# ece411_t2_schematic_11_15.net
KiCad netlist of a schematic drawn in EAGLE
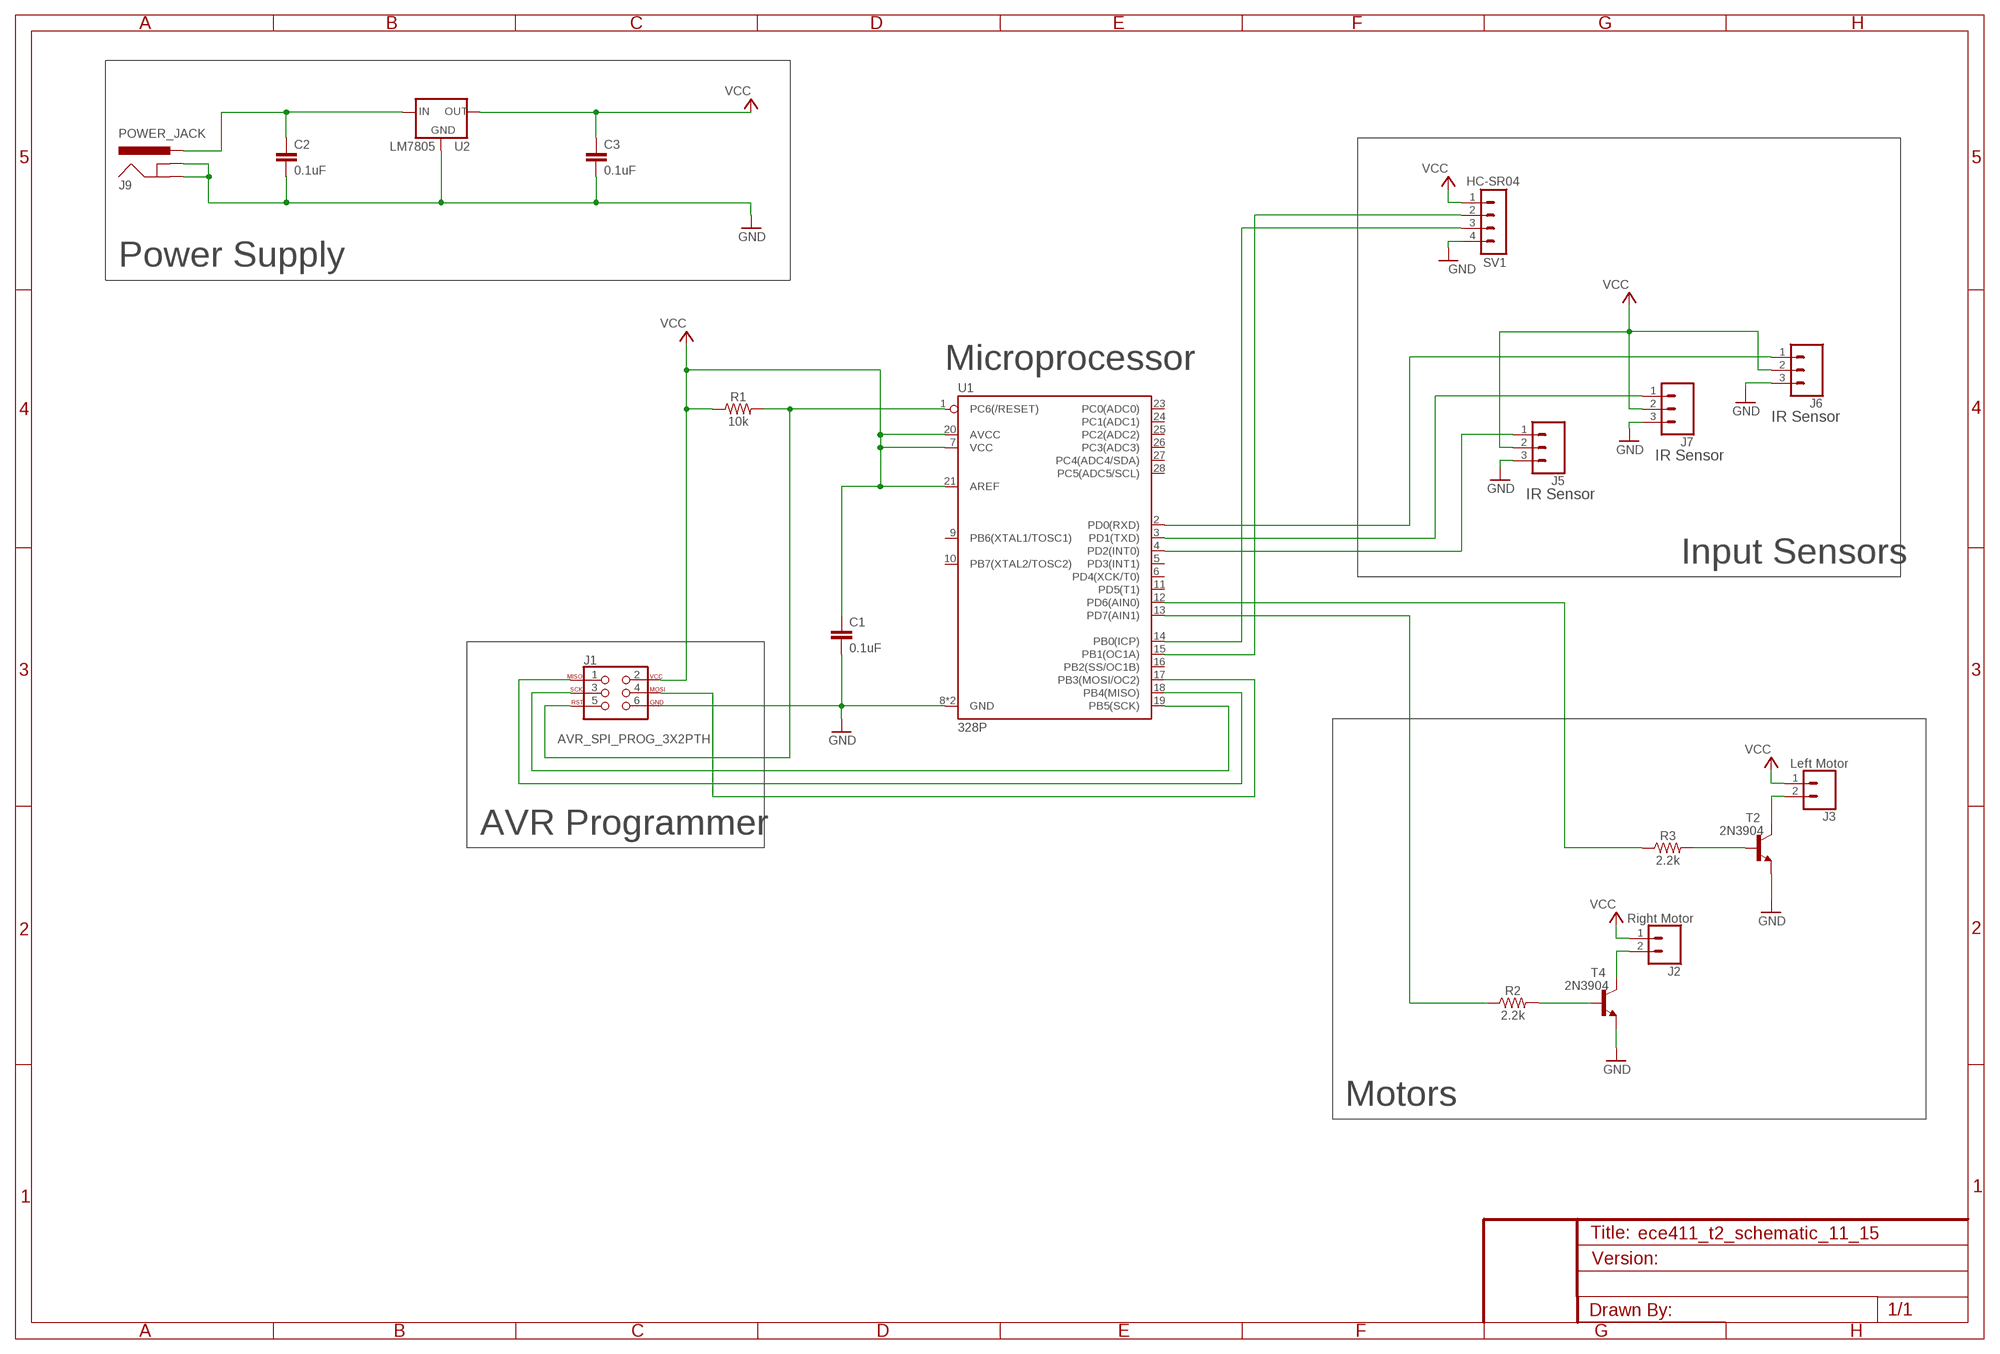
[diagram p0: schematic, sheet 1]

(export (version "E")
  (design (tool "Eeschema 10.0.6"))
  (components
    (comp (ref "C1")
      (value "0.1uF")
      (footprint "eagle-import:0402")
      (libsource (lib "eagle-import") (part "0.1UF-0402-6.3V-10%-X7R"))
    )
    (comp (ref "C2")
      (value "0.1uF")
      (footprint "eagle-import:0402")
      (libsource (lib "eagle-import") (part "0.1UF-0402-6.3V-10%-X7R"))
    )
    (comp (ref "C3")
      (value "0.1uF")
      (footprint "eagle-import:0402")
      (libsource (lib "eagle-import") (part "0.1UF-0402-6.3V-10%-X7R"))
    )
    (comp (ref "J1")
      (value "AVR_SPI_PROG_3X2PTH")
      (footprint "eagle-import:2X3")
      (libsource (lib "eagle-import") (part "AVR_SPI_PROG_3X2PTH"))
    )
    (comp (ref "J2")
      (value "Right Motor")
      (footprint "eagle-import:1X02")
      (libsource (lib "eagle-import") (part "CONN_02"))
    )
    (comp (ref "J3")
      (value "Left Motor")
      (footprint "eagle-import:1X02")
      (libsource (lib "eagle-import") (part "CONN_02"))
    )
    (comp (ref "J5")
      (value "455-1750-1-ND")
      (footprint "eagle-import:1X03")
      (libsource (lib "eagle-import") (part "CONN_03"))
    )
    (comp (ref "J6")
      (value "455-1750-1-ND")
      (footprint "eagle-import:1X03")
      (libsource (lib "eagle-import") (part "CONN_03"))
    )
    (comp (ref "J7")
      (value "455-1750-1-ND")
      (footprint "eagle-import:1X03")
      (libsource (lib "eagle-import") (part "CONN_03"))
    )
    (comp (ref "J9")
      (value "POWER_JACK")
      (footprint "eagle-import:POWER_JACK_PTH")
      (libsource (lib "eagle-import") (part "POWER_JACK"))
    )
    (comp (ref "R1")
      (value "10k")
      (footprint "eagle-import:0402")
      (libsource (lib "eagle-import") (part "10KOHM-0402-1/16W-1%"))
    )
    (comp (ref "R2")
      (value "2.2k")
      (footprint "eagle-import:0603")
      (libsource (lib "eagle-import") (part "2.2KOHM-0603-1/10W-1%"))
    )
    (comp (ref "R3")
      (value "2.2k")
      (footprint "eagle-import:0603")
      (libsource (lib "eagle-import") (part "2.2KOHM-0603-1/10W-1%"))
    )
    (comp (ref "SV1")
      (value "HC-SR04")
      (footprint "eagle-import:MA04-1")
      (libsource (lib "eagle-import") (part "MA04-1"))
    )
    (comp (ref "T2")
      (value "2N3904")
      (footprint "eagle-import:TO92")
      (libsource (lib "eagle-import") (part "2N3904"))
    )
    (comp (ref "T4")
      (value "2N3904")
      (footprint "eagle-import:TO92")
      (libsource (lib "eagle-import") (part "2N3904"))
    )
    (comp (ref "U1")
      (value "328P")
      (footprint "eagle-import:DIP28")
      (libsource (lib "eagle-import") (part "ATMEGA328P_PDIP"))
    )
    (comp (ref "U2")
      (value "LM7805")
      (footprint "eagle-import:TO-220-ALT")
      (libsource (lib "eagle-import") (part "V_REG_78XX-TO-220"))
    )
  )
  (nets
    (net (code "1") (name "GND") (class "Default")
      (node (ref "C1") (pin "2") (pinfunction "2_2") (pintype "passive"))
      (node (ref "C2") (pin "2") (pinfunction "2_2") (pintype "passive"))
      (node (ref "C3") (pin "2") (pinfunction "2_2") (pintype "passive"))
      (node (ref "J1") (pin "6") (pinfunction "6_6") (pintype "passive"))
      (node (ref "J5") (pin "3") (pinfunction "3_3") (pintype "passive"))
      (node (ref "J6") (pin "3") (pinfunction "3_3") (pintype "passive"))
      (node (ref "J7") (pin "3") (pinfunction "3_3") (pintype "passive"))
      (node (ref "J9") (pin "GND") (pinfunction "GND_GND") (pintype "bidirectional"))
      (node (ref "J9") (pin "GNDBREAK") (pinfunction "GNDBREAK_GNDBREAK") (pintype "bidirectional"))
      (node (ref "SV1") (pin "4") (pinfunction "4_4") (pintype "passive"))
      (node (ref "T2") (pin "3") (pinfunction "E_3") (pintype "passive"))
      (node (ref "T4") (pin "3") (pinfunction "E_3") (pintype "passive"))
      (node (ref "U1") (pin "22") (pinfunction "GND_22") (pintype "bidirectional"))
      (node (ref "U1") (pin "8") (pinfunction "GND_8") (pintype "bidirectional"))
      (node (ref "U2") (pin "GND") (pinfunction "GND_GND") (pintype "input"))
    )
    (net (code "2") (name "Net-(C2-Pad1)") (class "Default")
      (node (ref "C2") (pin "1") (pinfunction "1_1") (pintype "passive"))
      (node (ref "J9") (pin "PWR") (pinfunction "PWR_PWR") (pintype "bidirectional"))
      (node (ref "U2") (pin "IN") (pinfunction "IN_IN") (pintype "input"))
    )
    (net (code "3") (name "Net-(T2-B)") (class "Default")
      (node (ref "R3") (pin "2") (pinfunction "2_2") (pintype "passive"))
      (node (ref "T2") (pin "2") (pinfunction "B_2") (pintype "passive"))
    )
    (net (code "4") (name "Net-(T2-C)") (class "Default")
      (node (ref "J3") (pin "2") (pinfunction "2_2") (pintype "passive"))
      (node (ref "T2") (pin "1") (pinfunction "C_1") (pintype "passive"))
    )
    (net (code "5") (name "Net-(T4-B)") (class "Default")
      (node (ref "R2") (pin "2") (pinfunction "2_2") (pintype "passive"))
      (node (ref "T4") (pin "2") (pinfunction "B_2") (pintype "passive"))
    )
    (net (code "6") (name "Net-(T4-C)") (class "Default")
      (node (ref "J2") (pin "2") (pinfunction "2_2") (pintype "passive"))
      (node (ref "T4") (pin "1") (pinfunction "C_1") (pintype "passive"))
    )
    (net (code "7") (name "Net-(U1-PB0(ICP))") (class "Default")
      (node (ref "SV1") (pin "3") (pinfunction "3_3") (pintype "passive"))
      (node (ref "U1") (pin "14") (pinfunction "PB0(ICP)_14") (pintype "bidirectional"))
    )
    (net (code "8") (name "Net-(U1-PB1(OC1A))") (class "Default")
      (node (ref "SV1") (pin "2") (pinfunction "2_2") (pintype "passive"))
      (node (ref "U1") (pin "15") (pinfunction "PB1(OC1A)_15") (pintype "bidirectional"))
    )
    (net (code "9") (name "Net-(U1-PB3(MOSI{slash}OC2))") (class "Default")
      (node (ref "J1") (pin "4") (pinfunction "4_4") (pintype "passive"))
      (node (ref "U1") (pin "17") (pinfunction "PB3(MOSI/OC2)_17") (pintype "bidirectional"))
    )
    (net (code "10") (name "Net-(U1-PB4(MISO))") (class "Default")
      (node (ref "J1") (pin "1") (pinfunction "1_1") (pintype "passive"))
      (node (ref "U1") (pin "18") (pinfunction "PB4(MISO)_18") (pintype "bidirectional"))
    )
    (net (code "11") (name "Net-(U1-PB5(SCK))") (class "Default")
      (node (ref "J1") (pin "3") (pinfunction "3_3") (pintype "passive"))
      (node (ref "U1") (pin "19") (pinfunction "PB5(SCK)_19") (pintype "bidirectional"))
    )
    (net (code "12") (name "Net-(U1-PC6({slash}RESET))") (class "Default")
      (node (ref "J1") (pin "5") (pinfunction "5_5") (pintype "passive"))
      (node (ref "R1") (pin "2") (pinfunction "2_2") (pintype "passive"))
      (node (ref "U1") (pin "1") (pinfunction "PC6(/RESET)_1") (pintype "bidirectional"))
    )
    (net (code "13") (name "Net-(U1-PD0(RXD))") (class "Default")
      (node (ref "J6") (pin "1") (pinfunction "1_1") (pintype "passive"))
      (node (ref "U1") (pin "2") (pinfunction "PD0(RXD)_2") (pintype "bidirectional"))
    )
    (net (code "14") (name "Net-(U1-PD1(TXD))") (class "Default")
      (node (ref "J7") (pin "1") (pinfunction "1_1") (pintype "passive"))
      (node (ref "U1") (pin "3") (pinfunction "PD1(TXD)_3") (pintype "bidirectional"))
    )
    (net (code "15") (name "Net-(U1-PD2(INT0))") (class "Default")
      (node (ref "J5") (pin "1") (pinfunction "1_1") (pintype "passive"))
      (node (ref "U1") (pin "4") (pinfunction "PD2(INT0)_4") (pintype "bidirectional"))
    )
    (net (code "16") (name "Net-(U1-PD6(AIN0))") (class "Default")
      (node (ref "R3") (pin "1") (pinfunction "1_1") (pintype "passive"))
      (node (ref "U1") (pin "12") (pinfunction "PD6(AIN0)_12") (pintype "bidirectional"))
    )
    (net (code "17") (name "Net-(U1-PD7(AIN1))") (class "Default")
      (node (ref "R2") (pin "1") (pinfunction "1_1") (pintype "passive"))
      (node (ref "U1") (pin "13") (pinfunction "PD7(AIN1)_13") (pintype "bidirectional"))
    )
    (net (code "18") (name "VCC") (class "Default")
      (node (ref "C1") (pin "1") (pinfunction "1_1") (pintype "passive"))
      (node (ref "C3") (pin "1") (pinfunction "1_1") (pintype "passive"))
      (node (ref "J1") (pin "2") (pinfunction "2_2") (pintype "passive"))
      (node (ref "J2") (pin "1") (pinfunction "1_1") (pintype "passive"))
      (node (ref "J3") (pin "1") (pinfunction "1_1") (pintype "passive"))
      (node (ref "J5") (pin "2") (pinfunction "2_2") (pintype "passive"))
      (node (ref "J6") (pin "2") (pinfunction "2_2") (pintype "passive"))
      (node (ref "J7") (pin "2") (pinfunction "2_2") (pintype "passive"))
      (node (ref "R1") (pin "1") (pinfunction "1_1") (pintype "passive"))
      (node (ref "SV1") (pin "1") (pinfunction "1_1") (pintype "passive"))
      (node (ref "U1") (pin "20") (pinfunction "AVCC_20") (pintype "bidirectional"))
      (node (ref "U1") (pin "21") (pinfunction "AREF_21") (pintype "bidirectional"))
      (node (ref "U1") (pin "7") (pinfunction "VCC_7") (pintype "bidirectional"))
      (node (ref "U2") (pin "OUT") (pinfunction "OUT_OUT") (pintype "passive"))
    )
    (net (code "19") (name "unconnected-(U1-PB2(SS{slash}OC1B)-Pad16)") (class "Default")
      (node (ref "U1") (pin "16") (pinfunction "PB2(SS/OC1B)_16") (pintype "bidirectional"))
    )
    (net (code "20") (name "unconnected-(U1-PB6(XTAL1{slash}TOSC1)-Pad9)") (class "Default")
      (node (ref "U1") (pin "9") (pinfunction "PB6(XTAL1/TOSC1)_9") (pintype "bidirectional"))
    )
    (net (code "21") (name "unconnected-(U1-PB7(XTAL2{slash}TOSC2)-Pad10)") (class "Default")
      (node (ref "U1") (pin "10") (pinfunction "PB7(XTAL2/TOSC2)_10") (pintype "bidirectional"))
    )
    (net (code "22") (name "unconnected-(U1-PC0(ADC0)-Pad23)") (class "Default")
      (node (ref "U1") (pin "23") (pinfunction "PC0(ADC0)_23") (pintype "bidirectional"))
    )
    (net (code "23") (name "unconnected-(U1-PC1(ADC1)-Pad24)") (class "Default")
      (node (ref "U1") (pin "24") (pinfunction "PC1(ADC1)_24") (pintype "bidirectional"))
    )
    (net (code "24") (name "unconnected-(U1-PC2(ADC2)-Pad25)") (class "Default")
      (node (ref "U1") (pin "25") (pinfunction "PC2(ADC2)_25") (pintype "bidirectional"))
    )
    (net (code "25") (name "unconnected-(U1-PC3(ADC3)-Pad26)") (class "Default")
      (node (ref "U1") (pin "26") (pinfunction "PC3(ADC3)_26") (pintype "bidirectional"))
    )
    (net (code "26") (name "unconnected-(U1-PC4(ADC4{slash}SDA)-Pad27)") (class "Default")
      (node (ref "U1") (pin "27") (pinfunction "PC4(ADC4/SDA)_27") (pintype "bidirectional"))
    )
    (net (code "27") (name "unconnected-(U1-PC5(ADC5{slash}SCL)-Pad28)") (class "Default")
      (node (ref "U1") (pin "28") (pinfunction "PC5(ADC5/SCL)_28") (pintype "bidirectional"))
    )
    (net (code "28") (name "unconnected-(U1-PD3(INT1)-Pad5)") (class "Default")
      (node (ref "U1") (pin "5") (pinfunction "PD3(INT1)_5") (pintype "bidirectional"))
    )
    (net (code "29") (name "unconnected-(U1-PD4(XCK{slash}T0)-Pad6)") (class "Default")
      (node (ref "U1") (pin "6") (pinfunction "PD4(XCK/T0)_6") (pintype "bidirectional"))
    )
    (net (code "30") (name "unconnected-(U1-PD5(T1)-Pad11)") (class "Default")
      (node (ref "U1") (pin "11") (pinfunction "PD5(T1)_11") (pintype "bidirectional"))
    )
  )
)
